# Atto_LED_Coaster_RevB.net
KiCad netlist of a schematic drawn in EAGLE
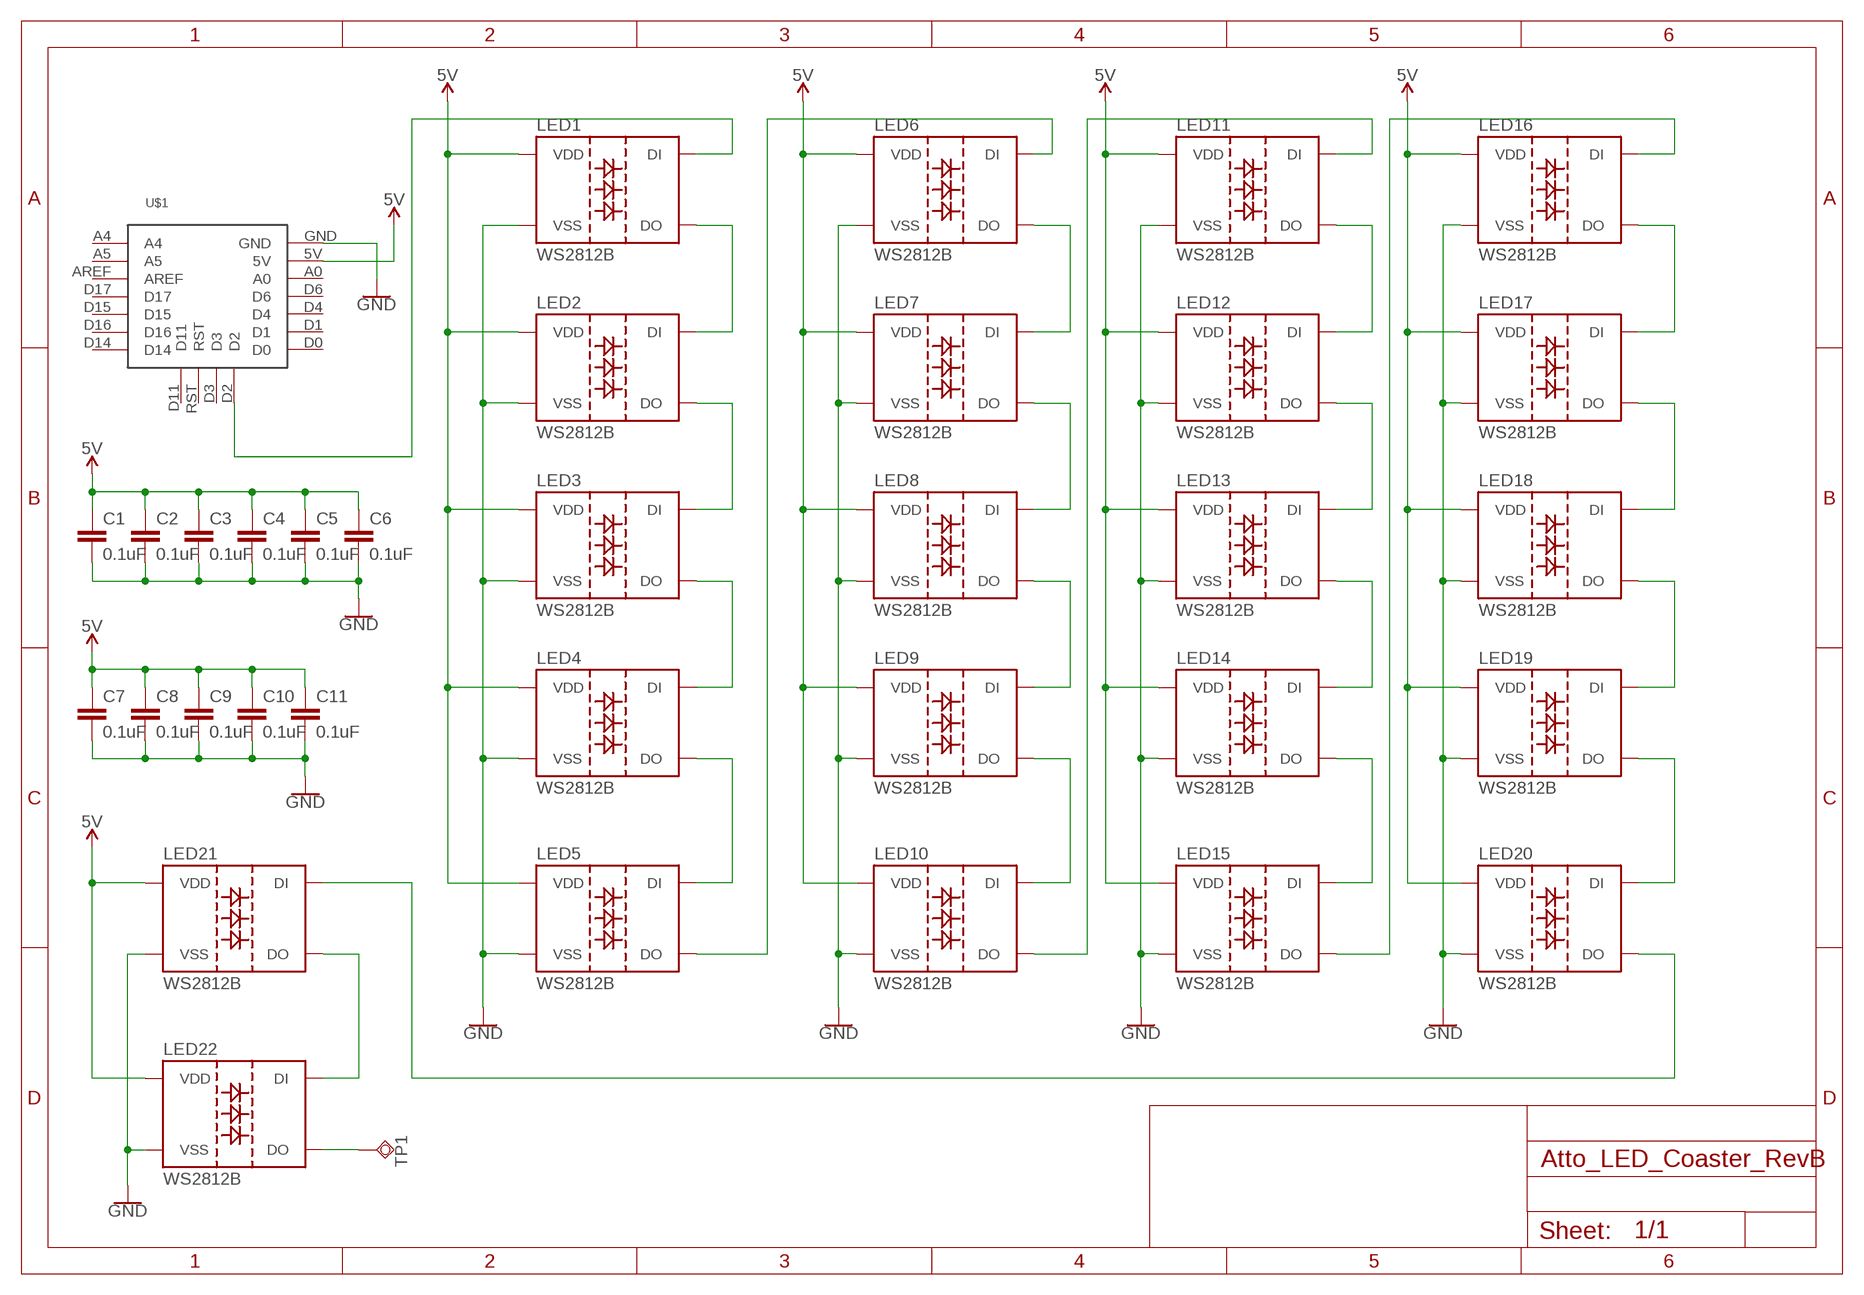
[diagram p0: schematic, sheet 1]

(export (version "E")
  (design (tool "Eeschema 10.0.6"))
  (components
    (comp (ref "C1")
      (value "0.1uF")
      (footprint "eagle-import:C0805")
      (libsource (lib "eagle-import") (part "C-EUC0805"))
    )
    (comp (ref "C2")
      (value "0.1uF")
      (footprint "eagle-import:C0805")
      (libsource (lib "eagle-import") (part "C-EUC0805"))
    )
    (comp (ref "C3")
      (value "0.1uF")
      (footprint "eagle-import:C0805")
      (libsource (lib "eagle-import") (part "C-EUC0805"))
    )
    (comp (ref "C4")
      (value "0.1uF")
      (footprint "eagle-import:C0805")
      (libsource (lib "eagle-import") (part "C-EUC0805"))
    )
    (comp (ref "C5")
      (value "0.1uF")
      (footprint "eagle-import:C0805")
      (libsource (lib "eagle-import") (part "C-EUC0805"))
    )
    (comp (ref "C6")
      (value "0.1uF")
      (footprint "eagle-import:C0805")
      (libsource (lib "eagle-import") (part "C-EUC0805"))
    )
    (comp (ref "C7")
      (value "0.1uF")
      (footprint "eagle-import:C0805")
      (libsource (lib "eagle-import") (part "C-EUC0805"))
    )
    (comp (ref "C8")
      (value "0.1uF")
      (footprint "eagle-import:C0805")
      (libsource (lib "eagle-import") (part "C-EUC0805"))
    )
    (comp (ref "C9")
      (value "0.1uF")
      (footprint "eagle-import:C0805")
      (libsource (lib "eagle-import") (part "C-EUC0805"))
    )
    (comp (ref "C10")
      (value "0.1uF")
      (footprint "eagle-import:C0805")
      (libsource (lib "eagle-import") (part "C-EUC0805"))
    )
    (comp (ref "C11")
      (value "0.1uF")
      (footprint "eagle-import:C0805")
      (libsource (lib "eagle-import") (part "C-EUC0805"))
    )
    (comp (ref "LED1")
      (value "WS2812B")
      (footprint "eagle-import:WS2812B")
      (libsource (lib "eagle-import") (part "WS2812B"))
    )
    (comp (ref "LED2")
      (value "WS2812B")
      (footprint "eagle-import:WS2812B")
      (libsource (lib "eagle-import") (part "WS2812B"))
    )
    (comp (ref "LED3")
      (value "WS2812B")
      (footprint "eagle-import:WS2812B")
      (libsource (lib "eagle-import") (part "WS2812B"))
    )
    (comp (ref "LED4")
      (value "WS2812B")
      (footprint "eagle-import:WS2812B")
      (libsource (lib "eagle-import") (part "WS2812B"))
    )
    (comp (ref "LED5")
      (value "WS2812B")
      (footprint "eagle-import:WS2812B")
      (libsource (lib "eagle-import") (part "WS2812B"))
    )
    (comp (ref "LED6")
      (value "WS2812B")
      (footprint "eagle-import:WS2812B")
      (libsource (lib "eagle-import") (part "WS2812B"))
    )
    (comp (ref "LED7")
      (value "WS2812B")
      (footprint "eagle-import:WS2812B")
      (libsource (lib "eagle-import") (part "WS2812B"))
    )
    (comp (ref "LED8")
      (value "WS2812B")
      (footprint "eagle-import:WS2812B")
      (libsource (lib "eagle-import") (part "WS2812B"))
    )
    (comp (ref "LED9")
      (value "WS2812B")
      (footprint "eagle-import:WS2812B")
      (libsource (lib "eagle-import") (part "WS2812B"))
    )
    (comp (ref "LED10")
      (value "WS2812B")
      (footprint "eagle-import:WS2812B")
      (libsource (lib "eagle-import") (part "WS2812B"))
    )
    (comp (ref "LED11")
      (value "WS2812B")
      (footprint "eagle-import:WS2812B")
      (fields (field (name "SPICEPREFIX") "E"))
      (libsource (lib "eagle-import") (part "WS2812B"))
    )
    (comp (ref "LED12")
      (value "WS2812B")
      (footprint "eagle-import:WS2812B")
      (libsource (lib "eagle-import") (part "WS2812B"))
    )
    (comp (ref "LED13")
      (value "WS2812B")
      (footprint "eagle-import:WS2812B")
      (libsource (lib "eagle-import") (part "WS2812B"))
    )
    (comp (ref "LED14")
      (value "WS2812B")
      (footprint "eagle-import:WS2812B")
      (libsource (lib "eagle-import") (part "WS2812B"))
    )
    (comp (ref "LED15")
      (value "WS2812B")
      (footprint "eagle-import:WS2812B")
      (libsource (lib "eagle-import") (part "WS2812B"))
    )
    (comp (ref "LED16")
      (value "WS2812B")
      (footprint "eagle-import:WS2812B")
      (libsource (lib "eagle-import") (part "WS2812B"))
    )
    (comp (ref "LED17")
      (value "WS2812B")
      (footprint "eagle-import:WS2812B")
      (libsource (lib "eagle-import") (part "WS2812B"))
    )
    (comp (ref "LED18")
      (value "WS2812B")
      (footprint "eagle-import:WS2812B")
      (libsource (lib "eagle-import") (part "WS2812B"))
    )
    (comp (ref "LED19")
      (value "WS2812B")
      (footprint "eagle-import:WS2812B")
      (libsource (lib "eagle-import") (part "WS2812B"))
    )
    (comp (ref "LED20")
      (value "WS2812B")
      (footprint "eagle-import:WS2812B")
      (libsource (lib "eagle-import") (part "WS2812B"))
    )
    (comp (ref "LED21")
      (value "WS2812B")
      (footprint "eagle-import:WS2812B")
      (libsource (lib "eagle-import") (part "WS2812B"))
    )
    (comp (ref "LED22")
      (value "WS2812B")
      (footprint "eagle-import:WS2812B")
      (libsource (lib "eagle-import") (part "WS2812B"))
    )
    (comp (ref "TP1")
      (value "TPSQTP20R")
      (footprint "eagle-import:TP20R")
      (libsource (lib "eagle-import") (part "TPSQTP20R"))
    )
    (comp (ref "U$1")
      (value "PIKSEY_ATTO")
      (footprint "eagle-import:PIKSEY_ATTO")
      (libsource (lib "eagle-import") (part "PIKSEY_ATTO"))
    )
  )
  (nets
    (net (code "1") (name "5V") (class "Default")
      (node (ref "C1") (pin "1") (pinfunction "1_1") (pintype "passive"))
      (node (ref "C10") (pin "1") (pinfunction "1_1") (pintype "passive"))
      (node (ref "C11") (pin "1") (pinfunction "1_1") (pintype "passive"))
      (node (ref "C2") (pin "1") (pinfunction "1_1") (pintype "passive"))
      (node (ref "C3") (pin "1") (pinfunction "1_1") (pintype "passive"))
      (node (ref "C4") (pin "1") (pinfunction "1_1") (pintype "passive"))
      (node (ref "C5") (pin "1") (pinfunction "1_1") (pintype "passive"))
      (node (ref "C6") (pin "1") (pinfunction "1_1") (pintype "passive"))
      (node (ref "C7") (pin "1") (pinfunction "1_1") (pintype "passive"))
      (node (ref "C8") (pin "1") (pinfunction "1_1") (pintype "passive"))
      (node (ref "C9") (pin "1") (pinfunction "1_1") (pintype "passive"))
      (node (ref "LED1") (pin "3") (pinfunction "VDD_3") (pintype "bidirectional"))
      (node (ref "LED10") (pin "3") (pinfunction "VDD_3") (pintype "bidirectional"))
      (node (ref "LED11") (pin "3") (pinfunction "VDD_3") (pintype "bidirectional"))
      (node (ref "LED12") (pin "3") (pinfunction "VDD_3") (pintype "bidirectional"))
      (node (ref "LED13") (pin "3") (pinfunction "VDD_3") (pintype "bidirectional"))
      (node (ref "LED14") (pin "3") (pinfunction "VDD_3") (pintype "bidirectional"))
      (node (ref "LED15") (pin "3") (pinfunction "VDD_3") (pintype "bidirectional"))
      (node (ref "LED16") (pin "3") (pinfunction "VDD_3") (pintype "bidirectional"))
      (node (ref "LED17") (pin "3") (pinfunction "VDD_3") (pintype "bidirectional"))
      (node (ref "LED18") (pin "3") (pinfunction "VDD_3") (pintype "bidirectional"))
      (node (ref "LED19") (pin "3") (pinfunction "VDD_3") (pintype "bidirectional"))
      (node (ref "LED2") (pin "3") (pinfunction "VDD_3") (pintype "bidirectional"))
      (node (ref "LED20") (pin "3") (pinfunction "VDD_3") (pintype "bidirectional"))
      (node (ref "LED21") (pin "3") (pinfunction "VDD_3") (pintype "bidirectional"))
      (node (ref "LED22") (pin "3") (pinfunction "VDD_3") (pintype "bidirectional"))
      (node (ref "LED3") (pin "3") (pinfunction "VDD_3") (pintype "bidirectional"))
      (node (ref "LED4") (pin "3") (pinfunction "VDD_3") (pintype "bidirectional"))
      (node (ref "LED5") (pin "3") (pinfunction "VDD_3") (pintype "bidirectional"))
      (node (ref "LED6") (pin "3") (pinfunction "VDD_3") (pintype "bidirectional"))
      (node (ref "LED7") (pin "3") (pinfunction "VDD_3") (pintype "bidirectional"))
      (node (ref "LED8") (pin "3") (pinfunction "VDD_3") (pintype "bidirectional"))
      (node (ref "LED9") (pin "3") (pinfunction "VDD_3") (pintype "bidirectional"))
      (node (ref "U$1") (pin "5V") (pinfunction "5V_5V") (pintype "bidirectional"))
    )
    (net (code "2") (name "GND") (class "Default")
      (node (ref "C1") (pin "2") (pinfunction "2_2") (pintype "passive"))
      (node (ref "C10") (pin "2") (pinfunction "2_2") (pintype "passive"))
      (node (ref "C11") (pin "2") (pinfunction "2_2") (pintype "passive"))
      (node (ref "C2") (pin "2") (pinfunction "2_2") (pintype "passive"))
      (node (ref "C3") (pin "2") (pinfunction "2_2") (pintype "passive"))
      (node (ref "C4") (pin "2") (pinfunction "2_2") (pintype "passive"))
      (node (ref "C5") (pin "2") (pinfunction "2_2") (pintype "passive"))
      (node (ref "C6") (pin "2") (pinfunction "2_2") (pintype "passive"))
      (node (ref "C7") (pin "2") (pinfunction "2_2") (pintype "passive"))
      (node (ref "C8") (pin "2") (pinfunction "2_2") (pintype "passive"))
      (node (ref "C9") (pin "2") (pinfunction "2_2") (pintype "passive"))
      (node (ref "LED1") (pin "1") (pinfunction "VSS_1") (pintype "bidirectional"))
      (node (ref "LED10") (pin "1") (pinfunction "VSS_1") (pintype "bidirectional"))
      (node (ref "LED11") (pin "1") (pinfunction "VSS_1") (pintype "bidirectional"))
      (node (ref "LED12") (pin "1") (pinfunction "VSS_1") (pintype "bidirectional"))
      (node (ref "LED13") (pin "1") (pinfunction "VSS_1") (pintype "bidirectional"))
      (node (ref "LED14") (pin "1") (pinfunction "VSS_1") (pintype "bidirectional"))
      (node (ref "LED15") (pin "1") (pinfunction "VSS_1") (pintype "bidirectional"))
      (node (ref "LED16") (pin "1") (pinfunction "VSS_1") (pintype "bidirectional"))
      (node (ref "LED17") (pin "1") (pinfunction "VSS_1") (pintype "bidirectional"))
      (node (ref "LED18") (pin "1") (pinfunction "VSS_1") (pintype "bidirectional"))
      (node (ref "LED19") (pin "1") (pinfunction "VSS_1") (pintype "bidirectional"))
      (node (ref "LED2") (pin "1") (pinfunction "VSS_1") (pintype "bidirectional"))
      (node (ref "LED20") (pin "1") (pinfunction "VSS_1") (pintype "bidirectional"))
      (node (ref "LED21") (pin "1") (pinfunction "VSS_1") (pintype "bidirectional"))
      (node (ref "LED22") (pin "1") (pinfunction "VSS_1") (pintype "bidirectional"))
      (node (ref "LED3") (pin "1") (pinfunction "VSS_1") (pintype "bidirectional"))
      (node (ref "LED4") (pin "1") (pinfunction "VSS_1") (pintype "bidirectional"))
      (node (ref "LED5") (pin "1") (pinfunction "VSS_1") (pintype "bidirectional"))
      (node (ref "LED6") (pin "1") (pinfunction "VSS_1") (pintype "bidirectional"))
      (node (ref "LED7") (pin "1") (pinfunction "VSS_1") (pintype "bidirectional"))
      (node (ref "LED8") (pin "1") (pinfunction "VSS_1") (pintype "bidirectional"))
      (node (ref "LED9") (pin "1") (pinfunction "VSS_1") (pintype "bidirectional"))
      (node (ref "U$1") (pin "GND") (pinfunction "GND_GND") (pintype "bidirectional"))
    )
    (net (code "3") (name "Net-(LED1-DI)") (class "Default")
      (node (ref "LED1") (pin "4") (pinfunction "DI_4") (pintype "bidirectional"))
      (node (ref "U$1") (pin "D2") (pinfunction "D2_D2") (pintype "bidirectional"))
    )
    (net (code "4") (name "Net-(LED1-DO)") (class "Default")
      (node (ref "LED1") (pin "2") (pinfunction "DO_2") (pintype "bidirectional"))
      (node (ref "LED2") (pin "4") (pinfunction "DI_4") (pintype "bidirectional"))
    )
    (net (code "5") (name "Net-(LED2-DO)") (class "Default")
      (node (ref "LED2") (pin "2") (pinfunction "DO_2") (pintype "bidirectional"))
      (node (ref "LED3") (pin "4") (pinfunction "DI_4") (pintype "bidirectional"))
    )
    (net (code "6") (name "Net-(LED3-DO)") (class "Default")
      (node (ref "LED3") (pin "2") (pinfunction "DO_2") (pintype "bidirectional"))
      (node (ref "LED4") (pin "4") (pinfunction "DI_4") (pintype "bidirectional"))
    )
    (net (code "7") (name "Net-(LED4-DO)") (class "Default")
      (node (ref "LED4") (pin "2") (pinfunction "DO_2") (pintype "bidirectional"))
      (node (ref "LED5") (pin "4") (pinfunction "DI_4") (pintype "bidirectional"))
    )
    (net (code "8") (name "Net-(LED5-DO)") (class "Default")
      (node (ref "LED5") (pin "2") (pinfunction "DO_2") (pintype "bidirectional"))
      (node (ref "LED6") (pin "4") (pinfunction "DI_4") (pintype "bidirectional"))
    )
    (net (code "9") (name "Net-(LED6-DO)") (class "Default")
      (node (ref "LED6") (pin "2") (pinfunction "DO_2") (pintype "bidirectional"))
      (node (ref "LED7") (pin "4") (pinfunction "DI_4") (pintype "bidirectional"))
    )
    (net (code "10") (name "Net-(LED7-DO)") (class "Default")
      (node (ref "LED7") (pin "2") (pinfunction "DO_2") (pintype "bidirectional"))
      (node (ref "LED8") (pin "4") (pinfunction "DI_4") (pintype "bidirectional"))
    )
    (net (code "11") (name "Net-(LED8-DO)") (class "Default")
      (node (ref "LED8") (pin "2") (pinfunction "DO_2") (pintype "bidirectional"))
      (node (ref "LED9") (pin "4") (pinfunction "DI_4") (pintype "bidirectional"))
    )
    (net (code "12") (name "Net-(LED10-DI)") (class "Default")
      (node (ref "LED10") (pin "4") (pinfunction "DI_4") (pintype "bidirectional"))
      (node (ref "LED9") (pin "2") (pinfunction "DO_2") (pintype "bidirectional"))
    )
    (net (code "13") (name "Net-(LED10-DO)") (class "Default")
      (node (ref "LED10") (pin "2") (pinfunction "DO_2") (pintype "bidirectional"))
      (node (ref "LED11") (pin "4") (pinfunction "DI_4") (pintype "bidirectional"))
    )
    (net (code "14") (name "Net-(LED11-DO)") (class "Default")
      (node (ref "LED11") (pin "2") (pinfunction "DO_2") (pintype "bidirectional"))
      (node (ref "LED12") (pin "4") (pinfunction "DI_4") (pintype "bidirectional"))
    )
    (net (code "15") (name "Net-(LED12-DO)") (class "Default")
      (node (ref "LED12") (pin "2") (pinfunction "DO_2") (pintype "bidirectional"))
      (node (ref "LED13") (pin "4") (pinfunction "DI_4") (pintype "bidirectional"))
    )
    (net (code "16") (name "Net-(LED13-DO)") (class "Default")
      (node (ref "LED13") (pin "2") (pinfunction "DO_2") (pintype "bidirectional"))
      (node (ref "LED14") (pin "4") (pinfunction "DI_4") (pintype "bidirectional"))
    )
    (net (code "17") (name "Net-(LED14-DO)") (class "Default")
      (node (ref "LED14") (pin "2") (pinfunction "DO_2") (pintype "bidirectional"))
      (node (ref "LED15") (pin "4") (pinfunction "DI_4") (pintype "bidirectional"))
    )
    (net (code "18") (name "Net-(LED15-DO)") (class "Default")
      (node (ref "LED15") (pin "2") (pinfunction "DO_2") (pintype "bidirectional"))
      (node (ref "LED16") (pin "4") (pinfunction "DI_4") (pintype "bidirectional"))
    )
    (net (code "19") (name "Net-(LED16-DO)") (class "Default")
      (node (ref "LED16") (pin "2") (pinfunction "DO_2") (pintype "bidirectional"))
      (node (ref "LED17") (pin "4") (pinfunction "DI_4") (pintype "bidirectional"))
    )
    (net (code "20") (name "Net-(LED17-DO)") (class "Default")
      (node (ref "LED17") (pin "2") (pinfunction "DO_2") (pintype "bidirectional"))
      (node (ref "LED18") (pin "4") (pinfunction "DI_4") (pintype "bidirectional"))
    )
    (net (code "21") (name "Net-(LED18-DO)") (class "Default")
      (node (ref "LED18") (pin "2") (pinfunction "DO_2") (pintype "bidirectional"))
      (node (ref "LED19") (pin "4") (pinfunction "DI_4") (pintype "bidirectional"))
    )
    (net (code "22") (name "Net-(LED19-DO)") (class "Default")
      (node (ref "LED19") (pin "2") (pinfunction "DO_2") (pintype "bidirectional"))
      (node (ref "LED20") (pin "4") (pinfunction "DI_4") (pintype "bidirectional"))
    )
    (net (code "23") (name "Net-(LED20-DO)") (class "Default")
      (node (ref "LED20") (pin "2") (pinfunction "DO_2") (pintype "bidirectional"))
      (node (ref "LED21") (pin "4") (pinfunction "DI_4") (pintype "bidirectional"))
    )
    (net (code "24") (name "Net-(LED21-DO)") (class "Default")
      (node (ref "LED21") (pin "2") (pinfunction "DO_2") (pintype "bidirectional"))
      (node (ref "LED22") (pin "4") (pinfunction "DI_4") (pintype "bidirectional"))
    )
    (net (code "25") (name "Net-(LED22-DO)") (class "Default")
      (node (ref "LED22") (pin "2") (pinfunction "DO_2") (pintype "bidirectional"))
      (node (ref "TP1") (pin "TP") (pinfunction "TP_TP") (pintype "input"))
    )
    (net (code "26") (name "unconnected-(U$1-PadA0)") (class "Default")
      (node (ref "U$1") (pin "A0") (pinfunction "A0_A0") (pintype "bidirectional"))
    )
    (net (code "27") (name "unconnected-(U$1-PadA4)") (class "Default")
      (node (ref "U$1") (pin "A4") (pinfunction "A4_A4") (pintype "bidirectional"))
    )
    (net (code "28") (name "unconnected-(U$1-PadA5)") (class "Default")
      (node (ref "U$1") (pin "A5") (pinfunction "A5_A5") (pintype "bidirectional"))
    )
    (net (code "29") (name "unconnected-(U$1-PadAREF)") (class "Default")
      (node (ref "U$1") (pin "AREF") (pinfunction "AREF_AREF") (pintype "bidirectional"))
    )
    (net (code "30") (name "unconnected-(U$1-PadD0)") (class "Default")
      (node (ref "U$1") (pin "D0") (pinfunction "D0_D0") (pintype "bidirectional"))
    )
    (net (code "31") (name "unconnected-(U$1-PadD1)") (class "Default")
      (node (ref "U$1") (pin "D1") (pinfunction "D1_D1") (pintype "bidirectional"))
    )
    (net (code "32") (name "unconnected-(U$1-PadD3)") (class "Default")
      (node (ref "U$1") (pin "D3") (pinfunction "D3_D3") (pintype "bidirectional"))
    )
    (net (code "33") (name "unconnected-(U$1-PadD4)") (class "Default")
      (node (ref "U$1") (pin "D4") (pinfunction "D4_D4") (pintype "bidirectional"))
    )
    (net (code "34") (name "unconnected-(U$1-PadD6)") (class "Default")
      (node (ref "U$1") (pin "D6") (pinfunction "D6_D6") (pintype "bidirectional"))
    )
    (net (code "35") (name "unconnected-(U$1-PadD11)") (class "Default")
      (node (ref "U$1") (pin "D11") (pinfunction "D11_D11") (pintype "bidirectional"))
    )
    (net (code "36") (name "unconnected-(U$1-PadD14)") (class "Default")
      (node (ref "U$1") (pin "D14") (pinfunction "D14_D14") (pintype "bidirectional"))
    )
    (net (code "37") (name "unconnected-(U$1-PadD15)") (class "Default")
      (node (ref "U$1") (pin "D15") (pinfunction "D15_D15") (pintype "bidirectional"))
    )
    (net (code "38") (name "unconnected-(U$1-PadD16)") (class "Default")
      (node (ref "U$1") (pin "D16") (pinfunction "D16_D16") (pintype "bidirectional"))
    )
    (net (code "39") (name "unconnected-(U$1-PadD17)") (class "Default")
      (node (ref "U$1") (pin "D17") (pinfunction "D17_D17") (pintype "bidirectional"))
    )
    (net (code "40") (name "unconnected-(U$1-PadRST)") (class "Default")
      (node (ref "U$1") (pin "RST") (pinfunction "RST_RST") (pintype "bidirectional"))
    )
  )
)
